# board.net
KiCad netlist of a schematic drawn in EAGLE
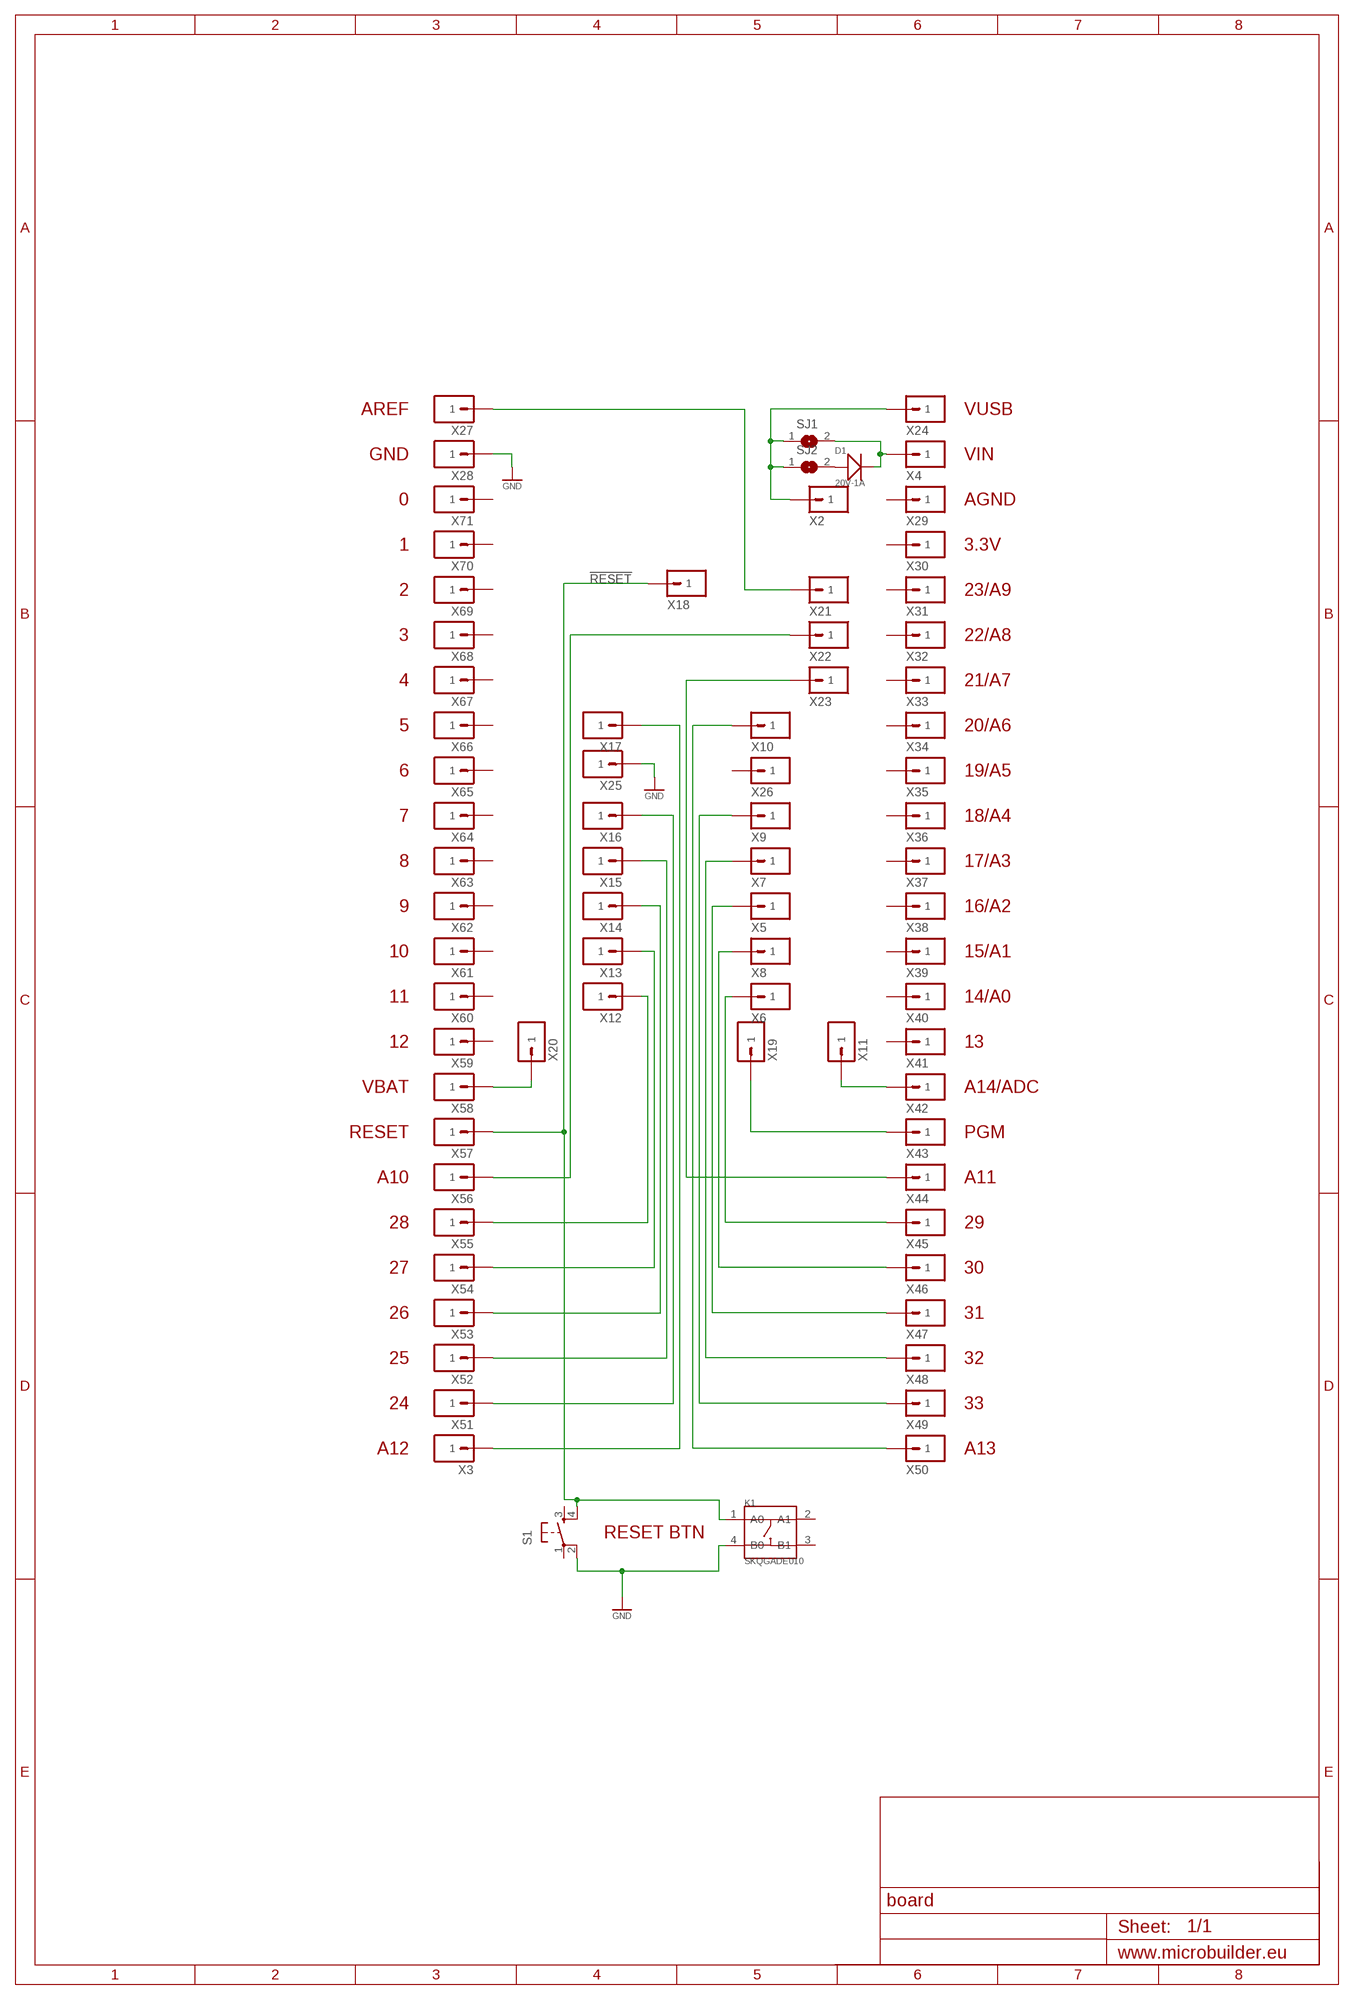
[diagram p0: schematic, sheet 1]

(export (version "E")
  (design (tool "Eeschema 10.0.6"))
  (components
    (comp (ref "D1")
      (value "20V-1A")
      (footprint "eagle-import:SOD-123")
      (fields (field (name "MPN") "B5819W"))
      (libsource (lib "eagle-import") (part "SMD-DIODE-SCHOTTKY-20V-1A(SOD-123)"))
    )
    (comp (ref "K1")
      (value "SKQGADE010")
      (footprint "eagle-import:SW4-SMD-5.2X5.2X1.5MM")
      (libsource (lib "eagle-import") (part "SMD-SWITCH-TOP-260GF(4P-D5.2MM)"))
    )
    (comp (ref "S1")
      (value "SWITCHPTH_NOSILK")
      (footprint "eagle-import:SWITCH_PTH_NOSILK")
      (libsource (lib "eagle-import") (part "SWITCHPTH_NOSILK"))
    )
    (comp (ref "SJ1")
      (value "SOLDERJUMPER")
      (footprint "eagle-import:SOLDERJUMPER_ARROW_NOPASTE")
      (libsource (lib "eagle-import") (part "SOLDERJUMPER"))
    )
    (comp (ref "SJ2")
      (value "SOLDERJUMPER")
      (footprint "eagle-import:SOLDERJUMPER_ARROW_NOPASTE")
      (libsource (lib "eagle-import") (part "SOLDERJUMPER"))
    )
    (comp (ref "X2")
      (value "1P1/MIN_NOSILK")
      (footprint "eagle-import:HEADER_1X1_1_MIN_NOSILK")
      (libsource (lib "eagle-import") (part "1P1/MIN_NOSILK"))
    )
    (comp (ref "X3")
      (value "1P1/MIN_NOSILK")
      (footprint "eagle-import:HEADER_1X1_1_MIN_NOSILK")
      (libsource (lib "eagle-import") (part "1P1/MIN_NOSILK"))
    )
    (comp (ref "X4")
      (value "1P1/MIN_NOSILK")
      (footprint "eagle-import:HEADER_1X1_1_MIN_NOSILK")
      (libsource (lib "eagle-import") (part "1P1/MIN_NOSILK"))
    )
    (comp (ref "X5")
      (value "1P")
      (footprint "eagle-import:1P_X")
      (libsource (lib "eagle-import") (part "1P"))
    )
    (comp (ref "X6")
      (value "1P")
      (footprint "eagle-import:1P_X")
      (libsource (lib "eagle-import") (part "1P"))
    )
    (comp (ref "X7")
      (value "1P")
      (footprint "eagle-import:1P_X")
      (libsource (lib "eagle-import") (part "1P"))
    )
    (comp (ref "X8")
      (value "1P")
      (footprint "eagle-import:1P_X")
      (libsource (lib "eagle-import") (part "1P"))
    )
    (comp (ref "X9")
      (value "1P")
      (footprint "eagle-import:1P_X")
      (libsource (lib "eagle-import") (part "1P"))
    )
    (comp (ref "X10")
      (value "1P")
      (footprint "eagle-import:1P_X")
      (libsource (lib "eagle-import") (part "1P"))
    )
    (comp (ref "X11")
      (value "1P1/MIN_NOSILK")
      (footprint "eagle-import:HEADER_1X1_1_MIN_NOSILK")
      (libsource (lib "eagle-import") (part "1P1/MIN_NOSILK"))
    )
    (comp (ref "X12")
      (value "1P")
      (footprint "eagle-import:1P_X")
      (libsource (lib "eagle-import") (part "1P"))
    )
    (comp (ref "X13")
      (value "1P")
      (footprint "eagle-import:1P_X")
      (libsource (lib "eagle-import") (part "1P"))
    )
    (comp (ref "X14")
      (value "1P")
      (footprint "eagle-import:1P_X")
      (libsource (lib "eagle-import") (part "1P"))
    )
    (comp (ref "X15")
      (value "1P")
      (footprint "eagle-import:1P_X")
      (libsource (lib "eagle-import") (part "1P"))
    )
    (comp (ref "X16")
      (value "1P")
      (footprint "eagle-import:1P_X")
      (libsource (lib "eagle-import") (part "1P"))
    )
    (comp (ref "X17")
      (value "1P")
      (footprint "eagle-import:1P_X")
      (libsource (lib "eagle-import") (part "1P"))
    )
    (comp (ref "X18")
      (value "1P")
      (footprint "eagle-import:1P_X")
      (libsource (lib "eagle-import") (part "1P"))
    )
    (comp (ref "X19")
      (value "1P1/MIN_NOSILK")
      (footprint "eagle-import:HEADER_1X1_1_MIN_NOSILK")
      (libsource (lib "eagle-import") (part "1P1/MIN_NOSILK"))
    )
    (comp (ref "X20")
      (value "1P1/MIN_NOSILK")
      (footprint "eagle-import:HEADER_1X1_1_MIN_NOSILK")
      (libsource (lib "eagle-import") (part "1P1/MIN_NOSILK"))
    )
    (comp (ref "X21")
      (value "1P1/MIN_NOSILK")
      (footprint "eagle-import:HEADER_1X1_1_MIN_NOSILK")
      (libsource (lib "eagle-import") (part "1P1/MIN_NOSILK"))
    )
    (comp (ref "X22")
      (value "1P1/MIN_NOSILK")
      (footprint "eagle-import:HEADER_1X1_1_MIN_NOSILK")
      (libsource (lib "eagle-import") (part "1P1/MIN_NOSILK"))
    )
    (comp (ref "X23")
      (value "1P1/MIN_NOSILK")
      (footprint "eagle-import:HEADER_1X1_1_MIN_NOSILK")
      (libsource (lib "eagle-import") (part "1P1/MIN_NOSILK"))
    )
    (comp (ref "X24")
      (value "1P1/MIN_NOSILK")
      (footprint "eagle-import:HEADER_1X1_1_MIN_NOSILK")
      (libsource (lib "eagle-import") (part "1P1/MIN_NOSILK"))
    )
    (comp (ref "X25")
      (value "1P")
      (footprint "eagle-import:1P_X")
      (libsource (lib "eagle-import") (part "1P"))
    )
    (comp (ref "X26")
      (value "1P")
      (footprint "eagle-import:1P_X")
      (libsource (lib "eagle-import") (part "1P"))
    )
    (comp (ref "X27")
      (value "1P1/MIN_NOSILK")
      (footprint "eagle-import:HEADER_1X1_1_MIN_NOSILK")
      (libsource (lib "eagle-import") (part "1P1/MIN_NOSILK"))
    )
    (comp (ref "X28")
      (value "1P1/MIN_NOSILK")
      (footprint "eagle-import:HEADER_1X1_1_MIN_NOSILK")
      (libsource (lib "eagle-import") (part "1P1/MIN_NOSILK"))
    )
    (comp (ref "X29")
      (value "1P1/MIN_NOSILK")
      (footprint "eagle-import:HEADER_1X1_1_MIN_NOSILK")
      (libsource (lib "eagle-import") (part "1P1/MIN_NOSILK"))
    )
    (comp (ref "X30")
      (value "1P1/MIN_NOSILK")
      (footprint "eagle-import:HEADER_1X1_1_MIN_NOSILK")
      (libsource (lib "eagle-import") (part "1P1/MIN_NOSILK"))
    )
    (comp (ref "X31")
      (value "1P1/MIN_NOSILK")
      (footprint "eagle-import:HEADER_1X1_1_MIN_NOSILK")
      (libsource (lib "eagle-import") (part "1P1/MIN_NOSILK"))
    )
    (comp (ref "X32")
      (value "1P1/MIN_NOSILK")
      (footprint "eagle-import:HEADER_1X1_1_MIN_NOSILK")
      (libsource (lib "eagle-import") (part "1P1/MIN_NOSILK"))
    )
    (comp (ref "X33")
      (value "1P1/MIN_NOSILK")
      (footprint "eagle-import:HEADER_1X1_1_MIN_NOSILK")
      (libsource (lib "eagle-import") (part "1P1/MIN_NOSILK"))
    )
    (comp (ref "X34")
      (value "1P1/MIN_NOSILK")
      (footprint "eagle-import:HEADER_1X1_1_MIN_NOSILK")
      (libsource (lib "eagle-import") (part "1P1/MIN_NOSILK"))
    )
    (comp (ref "X35")
      (value "1P1/MIN_NOSILK")
      (footprint "eagle-import:HEADER_1X1_1_MIN_NOSILK")
      (libsource (lib "eagle-import") (part "1P1/MIN_NOSILK"))
    )
    (comp (ref "X36")
      (value "1P1/MIN_NOSILK")
      (footprint "eagle-import:HEADER_1X1_1_MIN_NOSILK")
      (libsource (lib "eagle-import") (part "1P1/MIN_NOSILK"))
    )
    (comp (ref "X37")
      (value "1P1/MIN_NOSILK")
      (footprint "eagle-import:HEADER_1X1_1_MIN_NOSILK")
      (libsource (lib "eagle-import") (part "1P1/MIN_NOSILK"))
    )
    (comp (ref "X38")
      (value "1P1/MIN_NOSILK")
      (footprint "eagle-import:HEADER_1X1_1_MIN_NOSILK")
      (libsource (lib "eagle-import") (part "1P1/MIN_NOSILK"))
    )
    (comp (ref "X39")
      (value "1P1/MIN_NOSILK")
      (footprint "eagle-import:HEADER_1X1_1_MIN_NOSILK")
      (libsource (lib "eagle-import") (part "1P1/MIN_NOSILK"))
    )
    (comp (ref "X40")
      (value "1P1/MIN_NOSILK")
      (footprint "eagle-import:HEADER_1X1_1_MIN_NOSILK")
      (libsource (lib "eagle-import") (part "1P1/MIN_NOSILK"))
    )
    (comp (ref "X41")
      (value "1P1/MIN_NOSILK")
      (footprint "eagle-import:HEADER_1X1_1_MIN_NOSILK")
      (libsource (lib "eagle-import") (part "1P1/MIN_NOSILK"))
    )
    (comp (ref "X42")
      (value "1P1/MIN_NOSILK")
      (footprint "eagle-import:HEADER_1X1_1_MIN_NOSILK")
      (libsource (lib "eagle-import") (part "1P1/MIN_NOSILK"))
    )
    (comp (ref "X43")
      (value "1P1/MIN_NOSILK")
      (footprint "eagle-import:HEADER_1X1_1_MIN_NOSILK")
      (libsource (lib "eagle-import") (part "1P1/MIN_NOSILK"))
    )
    (comp (ref "X44")
      (value "1P1/MIN_NOSILK")
      (footprint "eagle-import:HEADER_1X1_1_MIN_NOSILK")
      (libsource (lib "eagle-import") (part "1P1/MIN_NOSILK"))
    )
    (comp (ref "X45")
      (value "1P1/MIN_NOSILK")
      (footprint "eagle-import:HEADER_1X1_1_MIN_NOSILK")
      (libsource (lib "eagle-import") (part "1P1/MIN_NOSILK"))
    )
    (comp (ref "X46")
      (value "1P1/MIN_NOSILK")
      (footprint "eagle-import:HEADER_1X1_1_MIN_NOSILK")
      (libsource (lib "eagle-import") (part "1P1/MIN_NOSILK"))
    )
    (comp (ref "X47")
      (value "1P1/MIN_NOSILK")
      (footprint "eagle-import:HEADER_1X1_1_MIN_NOSILK")
      (libsource (lib "eagle-import") (part "1P1/MIN_NOSILK"))
    )
    (comp (ref "X48")
      (value "1P1/MIN_NOSILK")
      (footprint "eagle-import:HEADER_1X1_1_MIN_NOSILK")
      (libsource (lib "eagle-import") (part "1P1/MIN_NOSILK"))
    )
    (comp (ref "X49")
      (value "1P1/MIN_NOSILK")
      (footprint "eagle-import:HEADER_1X1_1_MIN_NOSILK")
      (libsource (lib "eagle-import") (part "1P1/MIN_NOSILK"))
    )
    (comp (ref "X50")
      (value "1P1/MIN_NOSILK")
      (footprint "eagle-import:HEADER_1X1_1_MIN_NOSILK")
      (libsource (lib "eagle-import") (part "1P1/MIN_NOSILK"))
    )
    (comp (ref "X51")
      (value "1P1/MIN_NOSILK")
      (footprint "eagle-import:HEADER_1X1_1_MIN_NOSILK")
      (libsource (lib "eagle-import") (part "1P1/MIN_NOSILK"))
    )
    (comp (ref "X52")
      (value "1P1/MIN_NOSILK")
      (footprint "eagle-import:HEADER_1X1_1_MIN_NOSILK")
      (libsource (lib "eagle-import") (part "1P1/MIN_NOSILK"))
    )
    (comp (ref "X53")
      (value "1P1/MIN_NOSILK")
      (footprint "eagle-import:HEADER_1X1_1_MIN_NOSILK")
      (libsource (lib "eagle-import") (part "1P1/MIN_NOSILK"))
    )
    (comp (ref "X54")
      (value "1P1/MIN_NOSILK")
      (footprint "eagle-import:HEADER_1X1_1_MIN_NOSILK")
      (libsource (lib "eagle-import") (part "1P1/MIN_NOSILK"))
    )
    (comp (ref "X55")
      (value "1P1/MIN_NOSILK")
      (footprint "eagle-import:HEADER_1X1_1_MIN_NOSILK")
      (libsource (lib "eagle-import") (part "1P1/MIN_NOSILK"))
    )
    (comp (ref "X56")
      (value "1P1/MIN_NOSILK")
      (footprint "eagle-import:HEADER_1X1_1_MIN_NOSILK")
      (libsource (lib "eagle-import") (part "1P1/MIN_NOSILK"))
    )
    (comp (ref "X57")
      (value "1P1/MIN_NOSILK")
      (footprint "eagle-import:HEADER_1X1_1_MIN_NOSILK")
      (libsource (lib "eagle-import") (part "1P1/MIN_NOSILK"))
    )
    (comp (ref "X58")
      (value "1P1/MIN_NOSILK")
      (footprint "eagle-import:HEADER_1X1_1_MIN_NOSILK")
      (libsource (lib "eagle-import") (part "1P1/MIN_NOSILK"))
    )
    (comp (ref "X59")
      (value "1P1/MIN_NOSILK")
      (footprint "eagle-import:HEADER_1X1_1_MIN_NOSILK")
      (libsource (lib "eagle-import") (part "1P1/MIN_NOSILK"))
    )
    (comp (ref "X60")
      (value "1P1/MIN_NOSILK")
      (footprint "eagle-import:HEADER_1X1_1_MIN_NOSILK")
      (libsource (lib "eagle-import") (part "1P1/MIN_NOSILK"))
    )
    (comp (ref "X61")
      (value "1P1/MIN_NOSILK")
      (footprint "eagle-import:HEADER_1X1_1_MIN_NOSILK")
      (libsource (lib "eagle-import") (part "1P1/MIN_NOSILK"))
    )
    (comp (ref "X62")
      (value "1P1/MIN_NOSILK")
      (footprint "eagle-import:HEADER_1X1_1_MIN_NOSILK")
      (libsource (lib "eagle-import") (part "1P1/MIN_NOSILK"))
    )
    (comp (ref "X63")
      (value "1P1/MIN_NOSILK")
      (footprint "eagle-import:HEADER_1X1_1_MIN_NOSILK")
      (libsource (lib "eagle-import") (part "1P1/MIN_NOSILK"))
    )
    (comp (ref "X64")
      (value "1P1/MIN_NOSILK")
      (footprint "eagle-import:HEADER_1X1_1_MIN_NOSILK")
      (libsource (lib "eagle-import") (part "1P1/MIN_NOSILK"))
    )
    (comp (ref "X65")
      (value "1P1/MIN_NOSILK")
      (footprint "eagle-import:HEADER_1X1_1_MIN_NOSILK")
      (libsource (lib "eagle-import") (part "1P1/MIN_NOSILK"))
    )
    (comp (ref "X66")
      (value "1P1/MIN_NOSILK")
      (footprint "eagle-import:HEADER_1X1_1_MIN_NOSILK")
      (libsource (lib "eagle-import") (part "1P1/MIN_NOSILK"))
    )
    (comp (ref "X67")
      (value "1P1/MIN_NOSILK")
      (footprint "eagle-import:HEADER_1X1_1_MIN_NOSILK")
      (libsource (lib "eagle-import") (part "1P1/MIN_NOSILK"))
    )
    (comp (ref "X68")
      (value "1P1/MIN_NOSILK")
      (footprint "eagle-import:HEADER_1X1_1_MIN_NOSILK")
      (libsource (lib "eagle-import") (part "1P1/MIN_NOSILK"))
    )
    (comp (ref "X69")
      (value "1P1/MIN_NOSILK")
      (footprint "eagle-import:HEADER_1X1_1_MIN_NOSILK")
      (libsource (lib "eagle-import") (part "1P1/MIN_NOSILK"))
    )
    (comp (ref "X70")
      (value "1P1/MIN_NOSILK")
      (footprint "eagle-import:HEADER_1X1_1_MIN_NOSILK")
      (libsource (lib "eagle-import") (part "1P1/MIN_NOSILK"))
    )
    (comp (ref "X71")
      (value "1P1/MIN_NOSILK")
      (footprint "eagle-import:HEADER_1X1_1_MIN_NOSILK")
      (libsource (lib "eagle-import") (part "1P1/MIN_NOSILK"))
    )
  )
  (nets
    (net (code "1") (name "/~{RESET}") (class "Default")
      (node (ref "K1") (pin "1") (pinfunction "A0_1") (pintype "bidirectional"))
      (node (ref "S1") (pin "4") (pinfunction "4_4") (pintype "passive"))
      (node (ref "X18") (pin "1") (pinfunction "1_1") (pintype "passive"))
      (node (ref "X57") (pin "1") (pinfunction "1_1") (pintype "passive"))
    )
    (net (code "2") (name "GND") (class "Default")
      (node (ref "K1") (pin "4") (pinfunction "B0_4") (pintype "bidirectional"))
      (node (ref "S1") (pin "2") (pinfunction "2_2") (pintype "passive"))
      (node (ref "X25") (pin "1") (pinfunction "1_1") (pintype "passive"))
      (node (ref "X28") (pin "1") (pinfunction "1_1") (pintype "passive"))
    )
    (net (code "3") (name "Net-(D1-Pad+)") (class "Default")
      (node (ref "D1") (pin "+") (pinfunction "+_+") (pintype "passive"))
      (node (ref "SJ2") (pin "2") (pinfunction "2_2") (pintype "passive"))
    )
    (net (code "4") (name "Net-(D1-Pad-)") (class "Default")
      (node (ref "D1") (pin "-") (pinfunction "-_-") (pintype "passive"))
      (node (ref "SJ1") (pin "2") (pinfunction "2_2") (pintype "passive"))
      (node (ref "X4") (pin "1") (pinfunction "1_1") (pintype "passive"))
    )
    (net (code "5") (name "Net-(SJ1-Pad1)") (class "Default")
      (node (ref "SJ1") (pin "1") (pinfunction "1_1") (pintype "passive"))
      (node (ref "SJ2") (pin "1") (pinfunction "1_1") (pintype "passive"))
      (node (ref "X2") (pin "1") (pinfunction "1_1") (pintype "passive"))
      (node (ref "X24") (pin "1") (pinfunction "1_1") (pintype "passive"))
    )
    (net (code "6") (name "Net-(X10-Pad1)") (class "Default")
      (node (ref "X10") (pin "1") (pinfunction "1_1") (pintype "passive"))
      (node (ref "X50") (pin "1") (pinfunction "1_1") (pintype "passive"))
    )
    (net (code "7") (name "Net-(X11-Pad1)") (class "Default")
      (node (ref "X11") (pin "1") (pinfunction "1_1") (pintype "passive"))
      (node (ref "X42") (pin "1") (pinfunction "1_1") (pintype "passive"))
    )
    (net (code "8") (name "Net-(X12-Pad1)") (class "Default")
      (node (ref "X12") (pin "1") (pinfunction "1_1") (pintype "passive"))
      (node (ref "X55") (pin "1") (pinfunction "1_1") (pintype "passive"))
    )
    (net (code "9") (name "Net-(X13-Pad1)") (class "Default")
      (node (ref "X13") (pin "1") (pinfunction "1_1") (pintype "passive"))
      (node (ref "X54") (pin "1") (pinfunction "1_1") (pintype "passive"))
    )
    (net (code "10") (name "Net-(X14-Pad1)") (class "Default")
      (node (ref "X14") (pin "1") (pinfunction "1_1") (pintype "passive"))
      (node (ref "X53") (pin "1") (pinfunction "1_1") (pintype "passive"))
    )
    (net (code "11") (name "Net-(X15-Pad1)") (class "Default")
      (node (ref "X15") (pin "1") (pinfunction "1_1") (pintype "passive"))
      (node (ref "X52") (pin "1") (pinfunction "1_1") (pintype "passive"))
    )
    (net (code "12") (name "Net-(X16-Pad1)") (class "Default")
      (node (ref "X16") (pin "1") (pinfunction "1_1") (pintype "passive"))
      (node (ref "X51") (pin "1") (pinfunction "1_1") (pintype "passive"))
    )
    (net (code "13") (name "Net-(X17-Pad1)") (class "Default")
      (node (ref "X17") (pin "1") (pinfunction "1_1") (pintype "passive"))
      (node (ref "X3") (pin "1") (pinfunction "1_1") (pintype "passive"))
    )
    (net (code "14") (name "Net-(X19-Pad1)") (class "Default")
      (node (ref "X19") (pin "1") (pinfunction "1_1") (pintype "passive"))
      (node (ref "X43") (pin "1") (pinfunction "1_1") (pintype "passive"))
    )
    (net (code "15") (name "Net-(X20-Pad1)") (class "Default")
      (node (ref "X20") (pin "1") (pinfunction "1_1") (pintype "passive"))
      (node (ref "X58") (pin "1") (pinfunction "1_1") (pintype "passive"))
    )
    (net (code "16") (name "Net-(X21-Pad1)") (class "Default")
      (node (ref "X21") (pin "1") (pinfunction "1_1") (pintype "passive"))
      (node (ref "X27") (pin "1") (pinfunction "1_1") (pintype "passive"))
    )
    (net (code "17") (name "Net-(X22-Pad1)") (class "Default")
      (node (ref "X22") (pin "1") (pinfunction "1_1") (pintype "passive"))
      (node (ref "X56") (pin "1") (pinfunction "1_1") (pintype "passive"))
    )
    (net (code "18") (name "Net-(X23-Pad1)") (class "Default")
      (node (ref "X23") (pin "1") (pinfunction "1_1") (pintype "passive"))
      (node (ref "X44") (pin "1") (pinfunction "1_1") (pintype "passive"))
    )
    (net (code "19") (name "Net-(X45-Pad1)") (class "Default")
      (node (ref "X45") (pin "1") (pinfunction "1_1") (pintype "passive"))
      (node (ref "X6") (pin "1") (pinfunction "1_1") (pintype "passive"))
    )
    (net (code "20") (name "Net-(X46-Pad1)") (class "Default")
      (node (ref "X46") (pin "1") (pinfunction "1_1") (pintype "passive"))
      (node (ref "X8") (pin "1") (pinfunction "1_1") (pintype "passive"))
    )
    (net (code "21") (name "Net-(X47-Pad1)") (class "Default")
      (node (ref "X47") (pin "1") (pinfunction "1_1") (pintype "passive"))
      (node (ref "X5") (pin "1") (pinfunction "1_1") (pintype "passive"))
    )
    (net (code "22") (name "Net-(X48-Pad1)") (class "Default")
      (node (ref "X48") (pin "1") (pinfunction "1_1") (pintype "passive"))
      (node (ref "X7") (pin "1") (pinfunction "1_1") (pintype "passive"))
    )
    (net (code "23") (name "Net-(X49-Pad1)") (class "Default")
      (node (ref "X49") (pin "1") (pinfunction "1_1") (pintype "passive"))
      (node (ref "X9") (pin "1") (pinfunction "1_1") (pintype "passive"))
    )
    (net (code "24") (name "unconnected-(K1-A1-Pad2)") (class "Default")
      (node (ref "K1") (pin "2") (pinfunction "A1_2") (pintype "bidirectional"))
    )
    (net (code "25") (name "unconnected-(K1-B1-Pad3)") (class "Default")
      (node (ref "K1") (pin "3") (pinfunction "B1_3") (pintype "bidirectional"))
    )
    (net (code "26") (name "unconnected-(S1-Pad1)") (class "Default")
      (node (ref "S1") (pin "1") (pinfunction "1_1") (pintype "passive"))
    )
    (net (code "27") (name "unconnected-(S1-Pad3)") (class "Default")
      (node (ref "S1") (pin "3") (pinfunction "3_3") (pintype "passive"))
    )
    (net (code "28") (name "unconnected-(X26-Pad1)") (class "Default")
      (node (ref "X26") (pin "1") (pinfunction "1_1") (pintype "passive"))
    )
    (net (code "29") (name "unconnected-(X29-Pad1)") (class "Default")
      (node (ref "X29") (pin "1") (pinfunction "1_1") (pintype "passive"))
    )
    (net (code "30") (name "unconnected-(X30-Pad1)") (class "Default")
      (node (ref "X30") (pin "1") (pinfunction "1_1") (pintype "passive"))
    )
    (net (code "31") (name "unconnected-(X31-Pad1)") (class "Default")
      (node (ref "X31") (pin "1") (pinfunction "1_1") (pintype "passive"))
    )
    (net (code "32") (name "unconnected-(X32-Pad1)") (class "Default")
      (node (ref "X32") (pin "1") (pinfunction "1_1") (pintype "passive"))
    )
    (net (code "33") (name "unconnected-(X33-Pad1)") (class "Default")
      (node (ref "X33") (pin "1") (pinfunction "1_1") (pintype "passive"))
    )
    (net (code "34") (name "unconnected-(X34-Pad1)") (class "Default")
      (node (ref "X34") (pin "1") (pinfunction "1_1") (pintype "passive"))
    )
    (net (code "35") (name "unconnected-(X35-Pad1)") (class "Default")
      (node (ref "X35") (pin "1") (pinfunction "1_1") (pintype "passive"))
    )
    (net (code "36") (name "unconnected-(X36-Pad1)") (class "Default")
      (node (ref "X36") (pin "1") (pinfunction "1_1") (pintype "passive"))
    )
    (net (code "37") (name "unconnected-(X37-Pad1)") (class "Default")
      (node (ref "X37") (pin "1") (pinfunction "1_1") (pintype "passive"))
    )
    (net (code "38") (name "unconnected-(X38-Pad1)") (class "Default")
      (node (ref "X38") (pin "1") (pinfunction "1_1") (pintype "passive"))
    )
    (net (code "39") (name "unconnected-(X39-Pad1)") (class "Default")
      (node (ref "X39") (pin "1") (pinfunction "1_1") (pintype "passive"))
    )
    (net (code "40") (name "unconnected-(X40-Pad1)") (class "Default")
      (node (ref "X40") (pin "1") (pinfunction "1_1") (pintype "passive"))
    )
    (net (code "41") (name "unconnected-(X41-Pad1)") (class "Default")
      (node (ref "X41") (pin "1") (pinfunction "1_1") (pintype "passive"))
    )
    (net (code "42") (name "unconnected-(X59-Pad1)") (class "Default")
      (node (ref "X59") (pin "1") (pinfunction "1_1") (pintype "passive"))
    )
    (net (code "43") (name "unconnected-(X60-Pad1)") (class "Default")
      (node (ref "X60") (pin "1") (pinfunction "1_1") (pintype "passive"))
    )
    (net (code "44") (name "unconnected-(X61-Pad1)") (class "Default")
      (node (ref "X61") (pin "1") (pinfunction "1_1") (pintype "passive"))
    )
    (net (code "45") (name "unconnected-(X62-Pad1)") (class "Default")
      (node (ref "X62") (pin "1") (pinfunction "1_1") (pintype "passive"))
    )
    (net (code "46") (name "unconnected-(X63-Pad1)") (class "Default")
      (node (ref "X63") (pin "1") (pinfunction "1_1") (pintype "passive"))
    )
    (net (code "47") (name "unconnected-(X64-Pad1)") (class "Default")
      (node (ref "X64") (pin "1") (pinfunction "1_1") (pintype "passive"))
    )
    (net (code "48") (name "unconnected-(X65-Pad1)") (class "Default")
      (node (ref "X65") (pin "1") (pinfunction "1_1") (pintype "passive"))
    )
    (net (code "49") (name "unconnected-(X66-Pad1)") (class "Default")
      (node (ref "X66") (pin "1") (pinfunction "1_1") (pintype "passive"))
    )
    (net (code "50") (name "unconnected-(X67-Pad1)") (class "Default")
      (node (ref "X67") (pin "1") (pinfunction "1_1") (pintype "passive"))
    )
    (net (code "51") (name "unconnected-(X68-Pad1)") (class "Default")
      (node (ref "X68") (pin "1") (pinfunction "1_1") (pintype "passive"))
    )
    (net (code "52") (name "unconnected-(X69-Pad1)") (class "Default")
      (node (ref "X69") (pin "1") (pinfunction "1_1") (pintype "passive"))
    )
    (net (code "53") (name "unconnected-(X70-Pad1)") (class "Default")
      (node (ref "X70") (pin "1") (pinfunction "1_1") (pintype "passive"))
    )
    (net (code "54") (name "unconnected-(X71-Pad1)") (class "Default")
      (node (ref "X71") (pin "1") (pinfunction "1_1") (pintype "passive"))
    )
  )
)
